# Backplane.net
KiCad netlist of a schematic drawn in Altium Designer
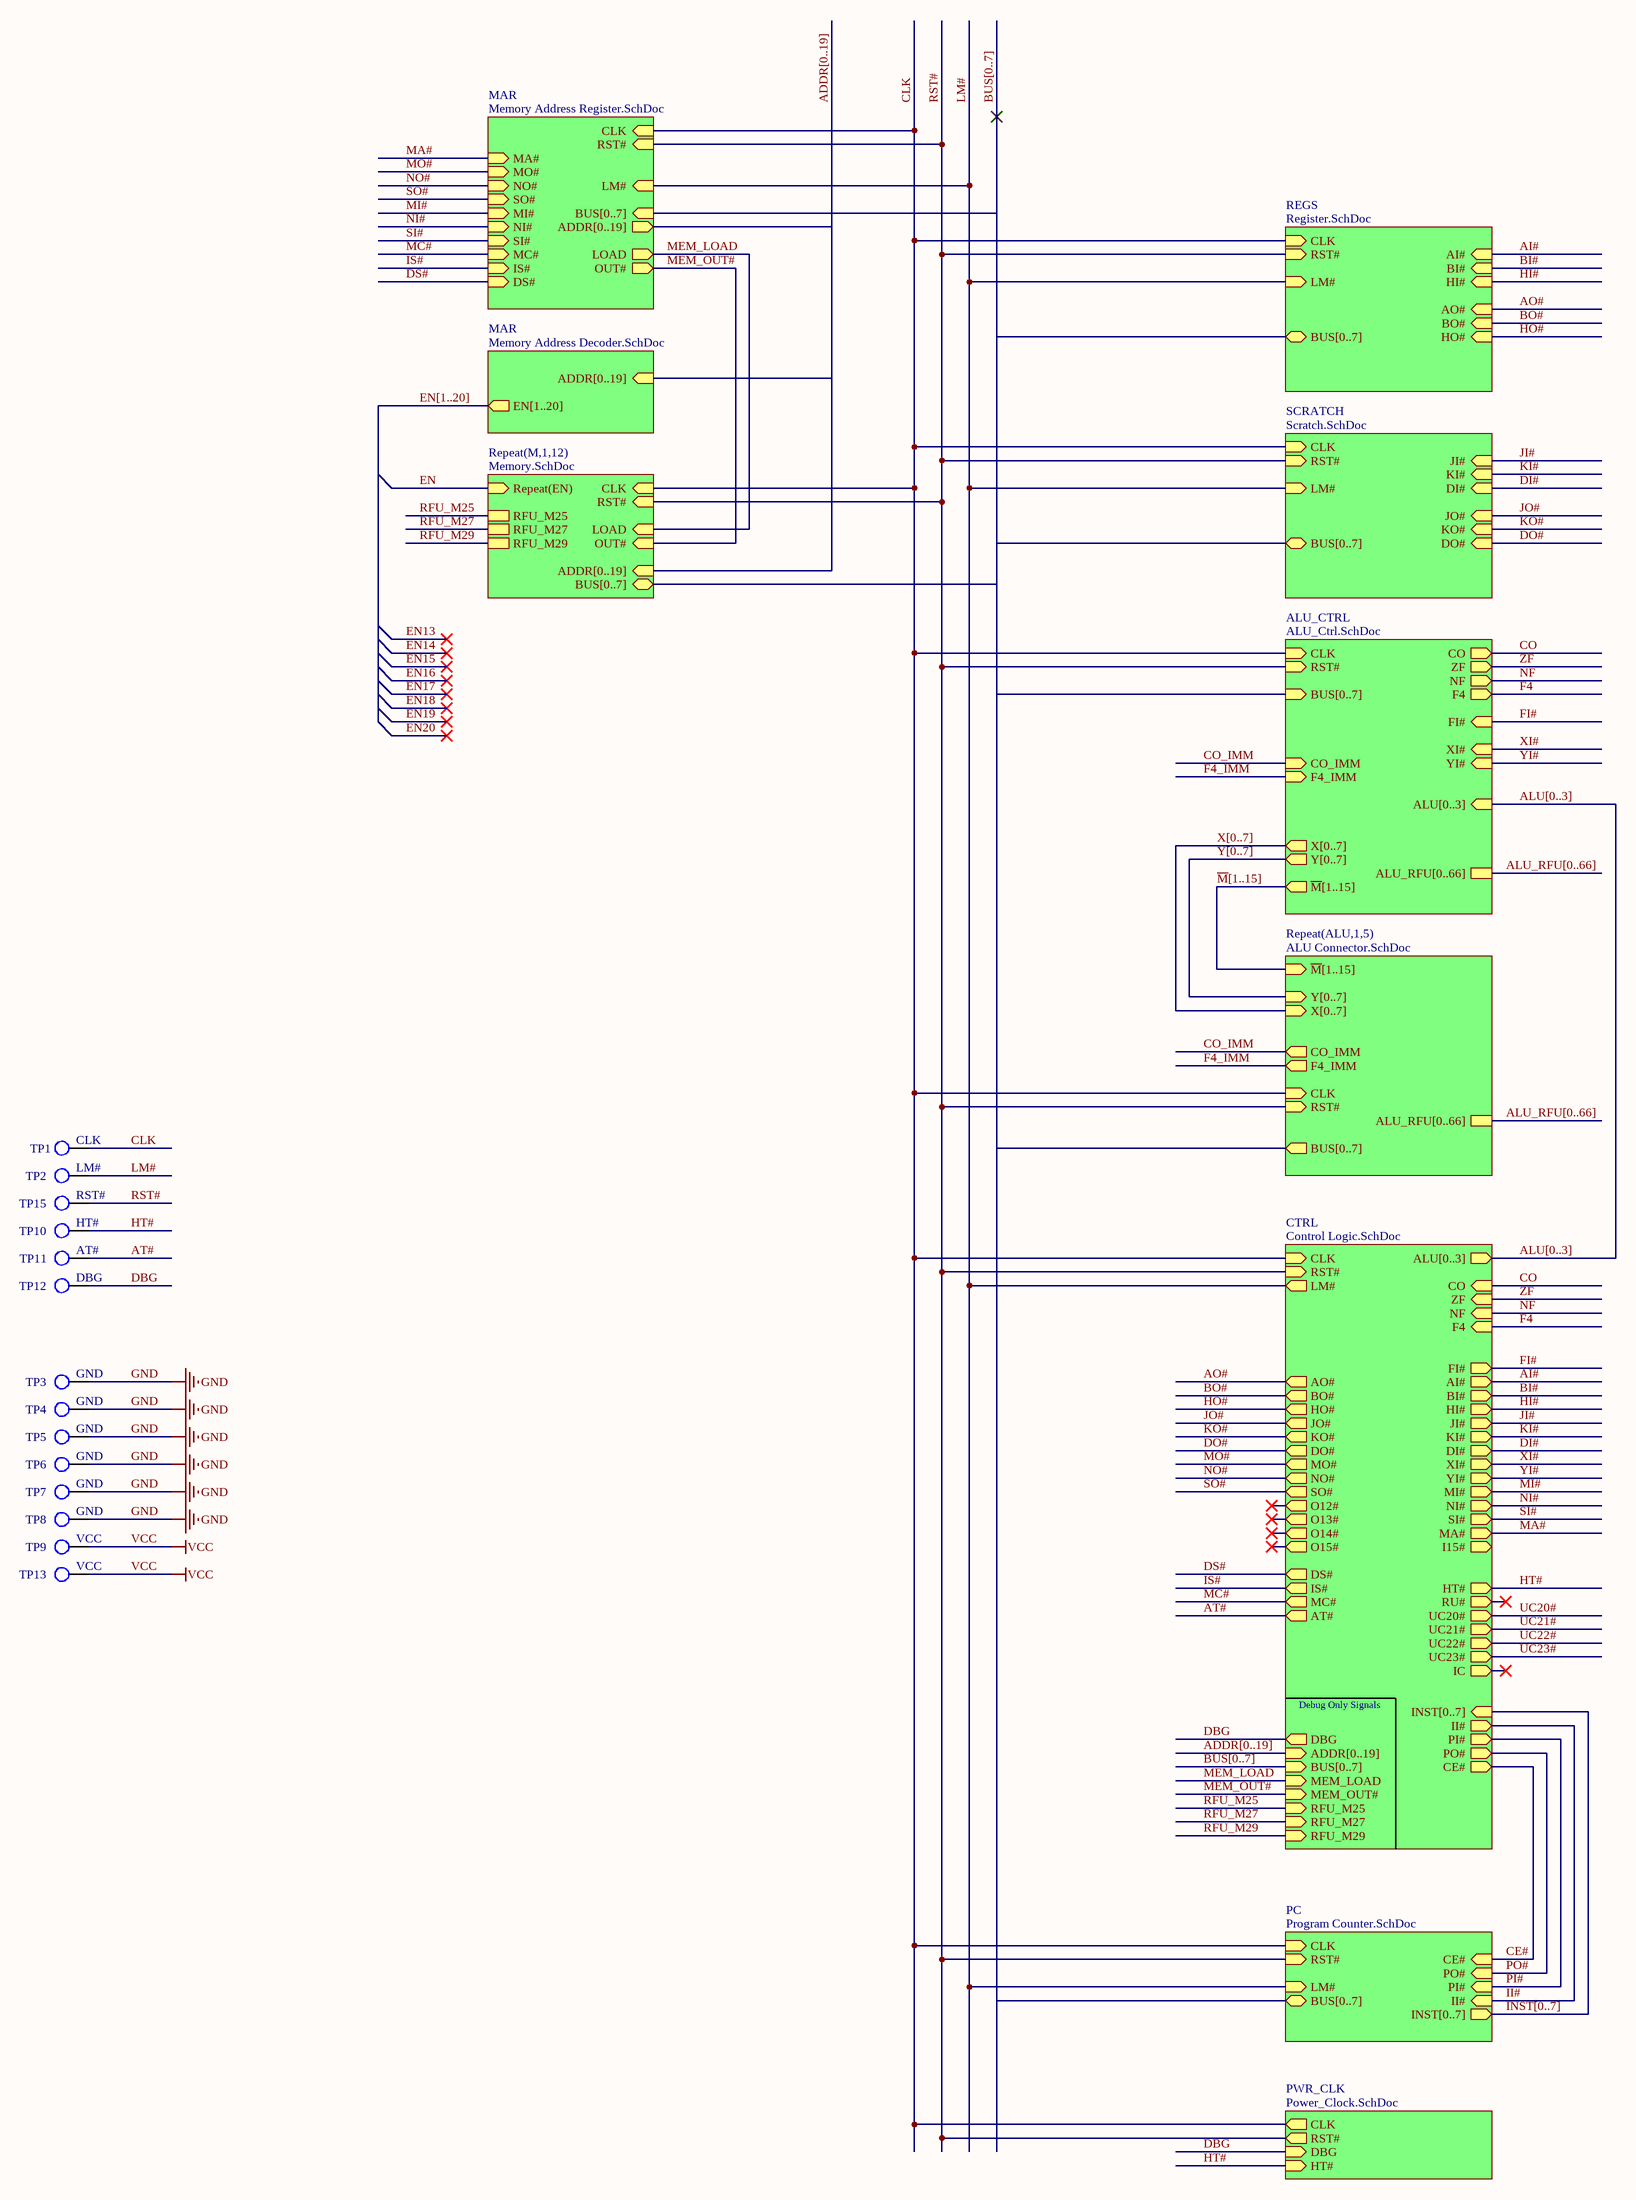
[diagram p0: Backplane.SchDoc]

(export (version "E")
  (design (tool "Eeschema 10.0.6"))
  (components
    (comp (ref "TP1") (value "CLK") (footprint "KSTN-5011_V") (libsource (lib "TP") (part "TP")))
    (comp (ref "TP2") (value "LM#") (footprint "KSTN-5011_V") (libsource (lib "TP") (part "TP")))
    (comp (ref "TP3") (value "GND") (footprint "KSTN-5011_V") (libsource (lib "TP") (part "TP")))
    (comp (ref "TP4") (value "GND") (footprint "KSTN-5011_V") (libsource (lib "TP") (part "TP")))
    (comp (ref "TP5") (value "GND") (footprint "KSTN-5011_V") (libsource (lib "TP") (part "TP")))
    (comp (ref "TP6") (value "GND") (footprint "KSTN-5011_V") (libsource (lib "TP") (part "TP")))
    (comp (ref "TP7") (value "GND") (footprint "KSTN-5011_V") (libsource (lib "TP") (part "TP")))
    (comp (ref "TP8") (value "GND") (footprint "KSTN-5011_V") (libsource (lib "TP") (part "TP")))
    (comp (ref "TP9") (value "VCC") (footprint "KSTN-5011_V") (libsource (lib "TP") (part "TP")))
    (comp (ref "TP10") (value "HT#") (footprint "KSTN-5011_V") (libsource (lib "TP") (part "TP")))
    (comp (ref "TP11") (value "AT#") (footprint "KSTN-5011_V") (libsource (lib "TP") (part "TP")))
    (comp (ref "TP12") (value "DBG") (footprint "KSTN-5011_V") (libsource (lib "TP") (part "TP")))
    (comp (ref "TP13") (value "VCC") (footprint "KSTN-5011_V") (libsource (lib "TP") (part "TP")))
    (comp (ref "TP15") (value "RST#") (footprint "KSTN-5011_V") (libsource (lib "TP") (part "TP")))
  )
  (nets
    (net (code "156") (name "/AT#") (class "Default") (node (ref "TP11") (pin "1") (pintype "passive")))
    (net (code "161") (name "/CLK") (class "Default") (node (ref "TP1") (pin "1") (pintype "passive")))
    (net (code "164") (name "/DBG") (class "Default") (node (ref "TP12") (pin "1") (pintype "passive")))
    (net (code "183") (name "/HT#") (class "Default") (node (ref "TP10") (pin "1") (pintype "passive")))
    (net (code "193") (name "/LM#") (class "Default") (node (ref "TP2") (pin "1") (pintype "passive")))
    (net (code "212") (name "/RST#") (class "Default") (node (ref "TP15") (pin "1") (pintype "passive")))
    (net (code "226") (name "GND") (class "Default")
      (node (ref "TP3") (pin "1") (pintype "passive"))
      (node (ref "TP4") (pin "1") (pintype "passive"))
      (node (ref "TP5") (pin "1") (pintype "passive"))
      (node (ref "TP6") (pin "1") (pintype "passive"))
      (node (ref "TP7") (pin "1") (pintype "passive"))
      (node (ref "TP8") (pin "1") (pintype "passive"))
    )
    (net (code "227") (name "VCC") (class "Default")
      (node (ref "TP13") (pin "1") (pintype "passive"))
      (node (ref "TP9") (pin "1") (pintype "passive"))
    )
  )
)
